# 03_POWER.net
KiCad netlist of a schematic drawn in Altium Designer
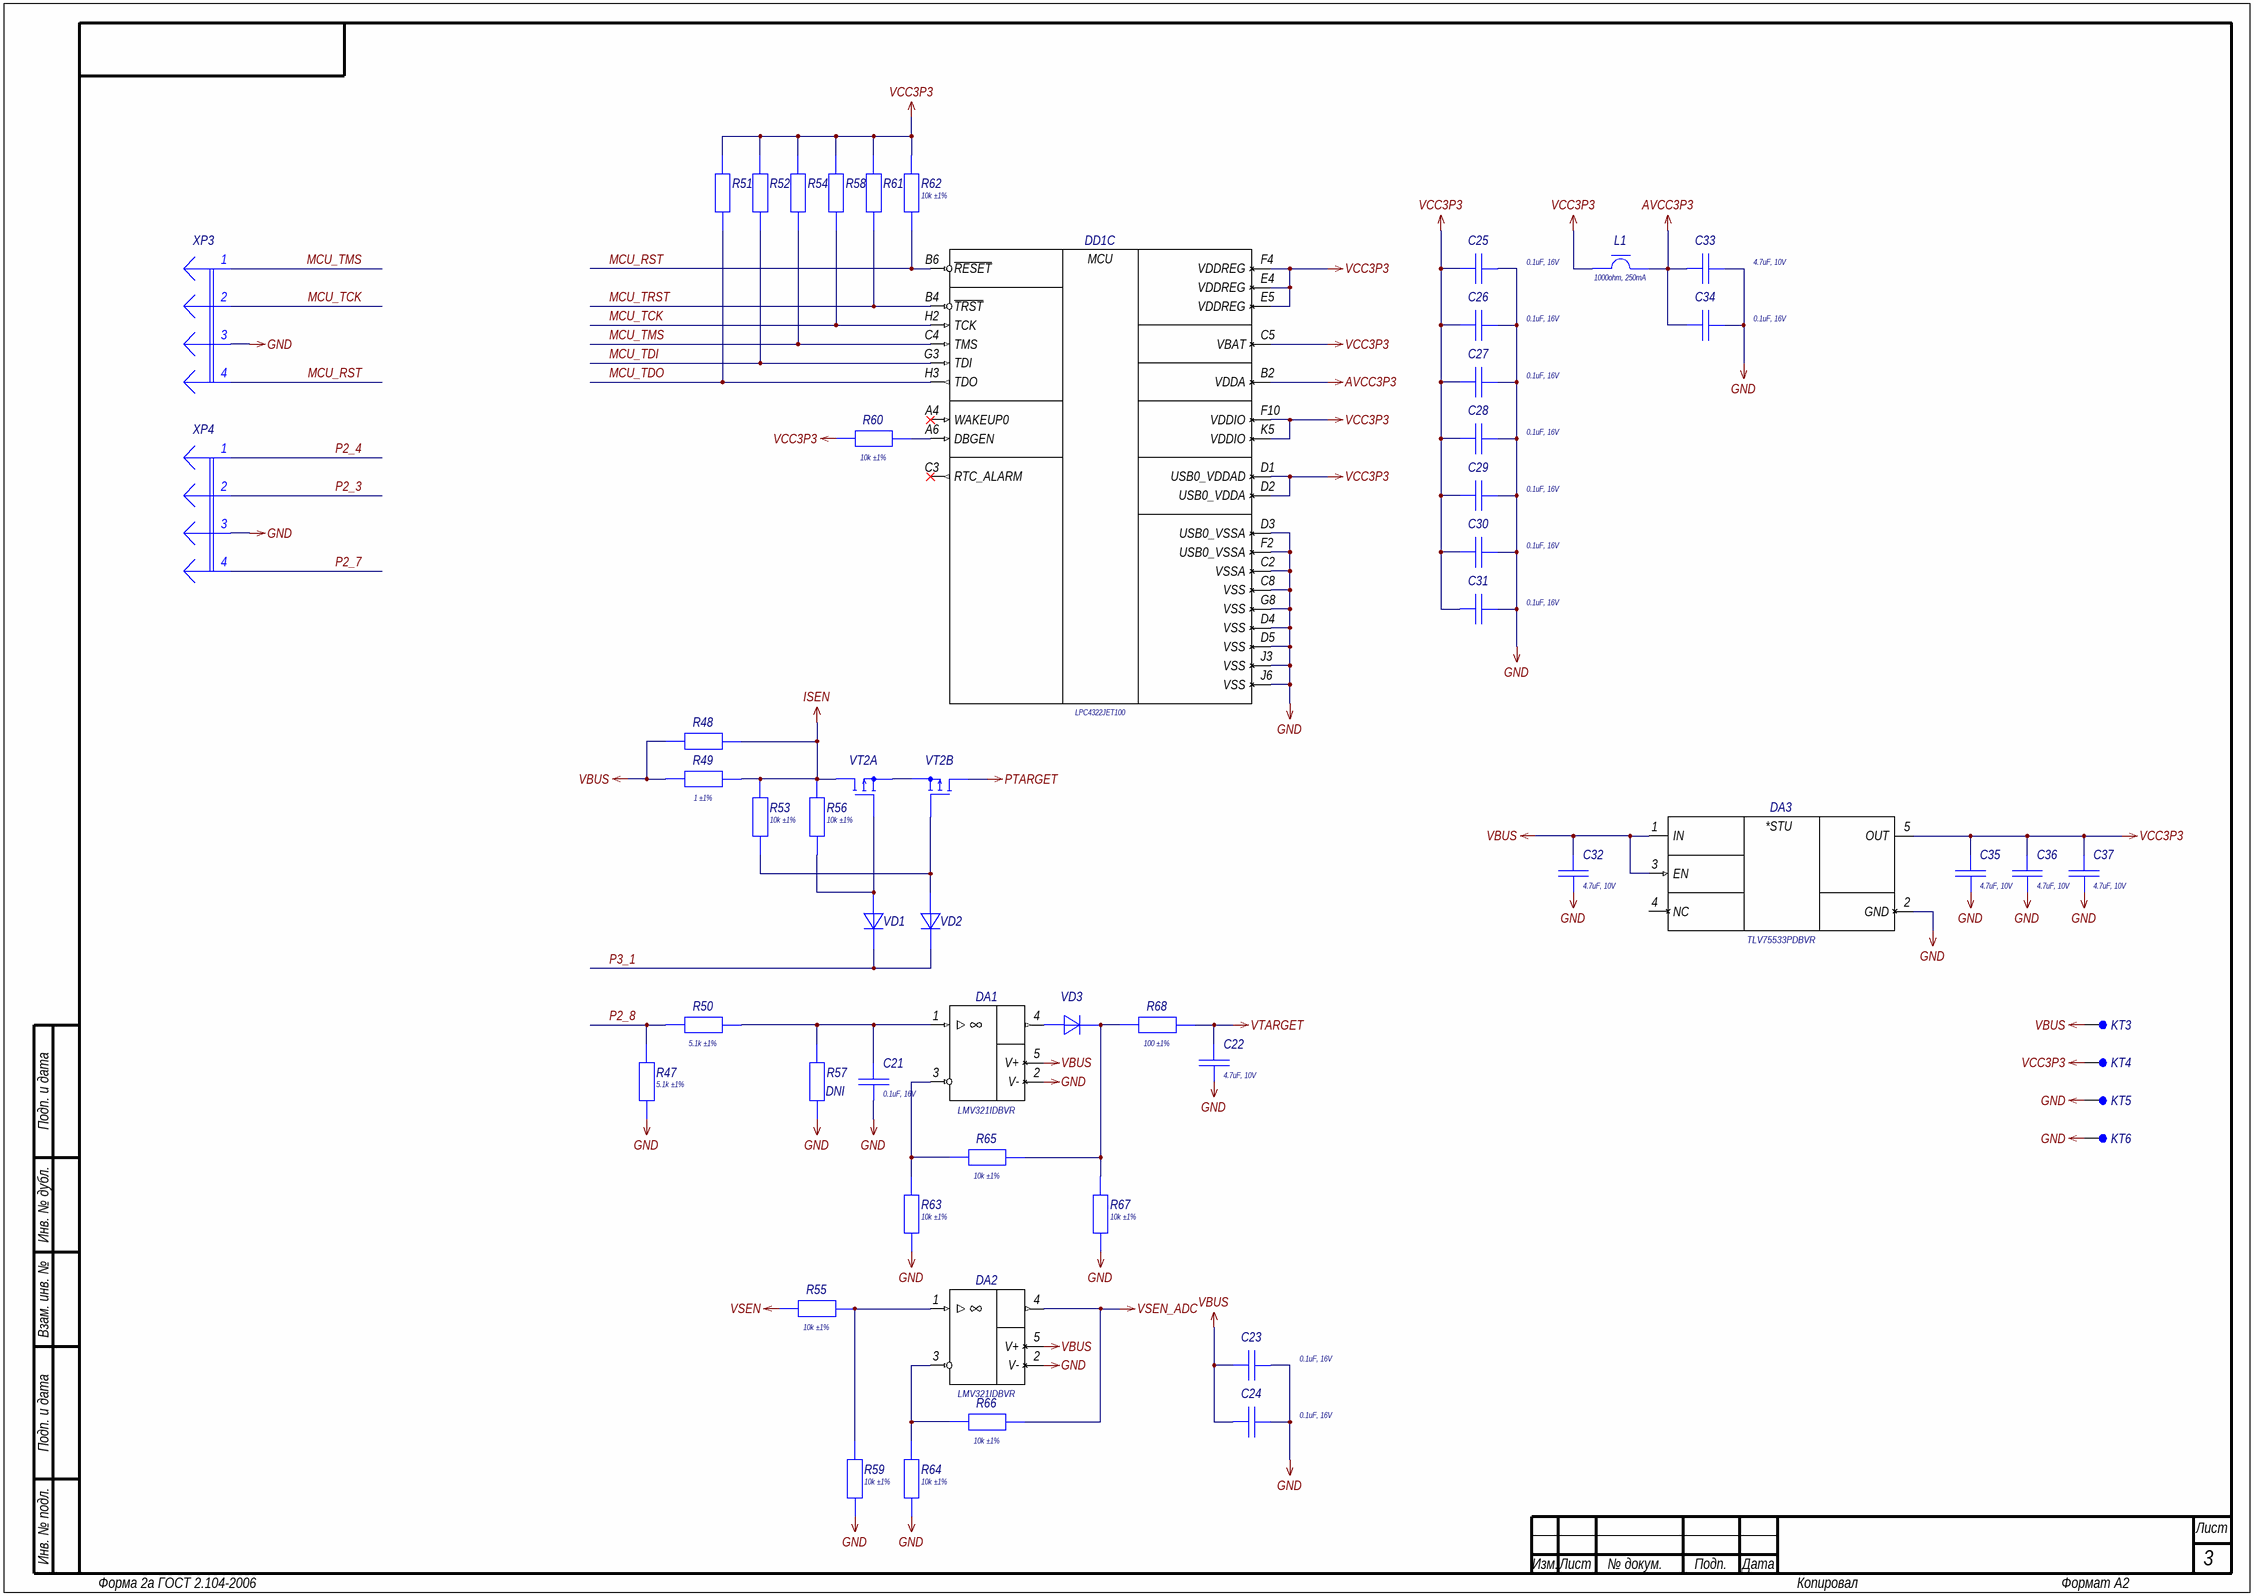
[diagram p0: 03_POWER.SchDoc]

(export (version "E")
  (design (tool "Eeschema 10.0.6"))
  (components
    (comp (ref "C21")
      (value "Capacitor")
      (footprint "C0402_100X050H050_H")
      (fields
        (field (name "PART NUMBER") "GCM155R71C104KA55D")
        (field (name "VOLTAGE") "16V")
        (field (name "TOLERANCE") "±10%")
        (field (name "SCHEMATIC VALUE") "0.1uF, 16V")
      )
      (libsource (lib "ADLib") (part "Capacitor"))
    )
    (comp (ref "C22")
      (value "Capacitor")
      (footprint "C0402_100X050H050_H")
      (fields
        (field (name "PART NUMBER") "GRM155R61A475MEAAD")
        (field (name "VOLTAGE") "10V")
        (field (name "TOLERANCE") "±20%")
        (field (name "SCHEMATIC VALUE") "4.7uF, 10V")
      )
      (libsource (lib "ADLib") (part "Capacitor"))
    )
    (comp (ref "C23")
      (value "Capacitor")
      (footprint "C0402_100X050H050_H")
      (fields
        (field (name "PART NUMBER") "GCM155R71C104KA55D")
        (field (name "VOLTAGE") "16V")
        (field (name "TOLERANCE") "±10%")
        (field (name "SCHEMATIC VALUE") "0.1uF, 16V")
      )
      (libsource (lib "ADLib") (part "Capacitor"))
    )
    (comp (ref "C24")
      (value "Capacitor")
      (footprint "C0402_100X050H050_H")
      (fields
        (field (name "PART NUMBER") "GCM155R71C104KA55D")
        (field (name "VOLTAGE") "16V")
        (field (name "TOLERANCE") "±10%")
        (field (name "SCHEMATIC VALUE") "0.1uF, 16V")
      )
      (libsource (lib "ADLib") (part "Capacitor"))
    )
    (comp (ref "C25")
      (value "Capacitor")
      (footprint "C0402_100X050H050_H")
      (fields
        (field (name "PART NUMBER") "GCM155R71C104KA55D")
        (field (name "VOLTAGE") "16V")
        (field (name "TOLERANCE") "±10%")
        (field (name "SCHEMATIC VALUE") "0.1uF, 16V")
      )
      (libsource (lib "ADLib") (part "Capacitor"))
    )
    (comp (ref "C26")
      (value "Capacitor")
      (footprint "C0402_100X050H050_H")
      (fields
        (field (name "PART NUMBER") "GCM155R71C104KA55D")
        (field (name "VOLTAGE") "16V")
        (field (name "TOLERANCE") "±10%")
        (field (name "SCHEMATIC VALUE") "0.1uF, 16V")
      )
      (libsource (lib "ADLib") (part "Capacitor"))
    )
    (comp (ref "C27")
      (value "Capacitor")
      (footprint "C0402_100X050H050_H")
      (fields
        (field (name "PART NUMBER") "GCM155R71C104KA55D")
        (field (name "VOLTAGE") "16V")
        (field (name "TOLERANCE") "±10%")
        (field (name "SCHEMATIC VALUE") "0.1uF, 16V")
      )
      (libsource (lib "ADLib") (part "Capacitor"))
    )
    (comp (ref "C28")
      (value "Capacitor")
      (footprint "C0402_100X050H050_H")
      (fields
        (field (name "PART NUMBER") "GCM155R71C104KA55D")
        (field (name "VOLTAGE") "16V")
        (field (name "TOLERANCE") "±10%")
        (field (name "SCHEMATIC VALUE") "0.1uF, 16V")
      )
      (libsource (lib "ADLib") (part "Capacitor"))
    )
    (comp (ref "C29")
      (value "Capacitor")
      (footprint "C0402_100X050H050_H")
      (fields
        (field (name "PART NUMBER") "GCM155R71C104KA55D")
        (field (name "VOLTAGE") "16V")
        (field (name "TOLERANCE") "±10%")
        (field (name "SCHEMATIC VALUE") "0.1uF, 16V")
      )
      (libsource (lib "ADLib") (part "Capacitor"))
    )
    (comp (ref "C30")
      (value "Capacitor")
      (footprint "C0402_100X050H050_H")
      (fields
        (field (name "PART NUMBER") "GCM155R71C104KA55D")
        (field (name "VOLTAGE") "16V")
        (field (name "TOLERANCE") "±10%")
        (field (name "SCHEMATIC VALUE") "0.1uF, 16V")
      )
      (libsource (lib "ADLib") (part "Capacitor"))
    )
    (comp (ref "C31")
      (value "Capacitor")
      (footprint "C0402_100X050H050_H")
      (fields
        (field (name "PART NUMBER") "GCM155R71C104KA55D")
        (field (name "VOLTAGE") "16V")
        (field (name "TOLERANCE") "±10%")
        (field (name "SCHEMATIC VALUE") "0.1uF, 16V")
      )
      (libsource (lib "ADLib") (part "Capacitor"))
    )
    (comp (ref "C32")
      (value "Capacitor")
      (footprint "C0402_100X050H050_H")
      (fields
        (field (name "PART NUMBER") "GRM155R61A475MEAAD")
        (field (name "VOLTAGE") "10V")
        (field (name "TOLERANCE") "±20%")
        (field (name "SCHEMATIC VALUE") "4.7uF, 10V")
      )
      (libsource (lib "ADLib") (part "Capacitor"))
    )
    (comp (ref "C33")
      (value "Capacitor")
      (footprint "C0402_100X050H050_H")
      (fields
        (field (name "PART NUMBER") "GRM155R61A475MEAAD")
        (field (name "VOLTAGE") "10V")
        (field (name "TOLERANCE") "±20%")
        (field (name "SCHEMATIC VALUE") "4.7uF, 10V")
      )
      (libsource (lib "ADLib") (part "Capacitor"))
    )
    (comp (ref "C34")
      (value "Capacitor")
      (footprint "C0402_100X050H050_H")
      (fields
        (field (name "PART NUMBER") "GCM155R71C104KA55D")
        (field (name "VOLTAGE") "16V")
        (field (name "TOLERANCE") "±10%")
        (field (name "SCHEMATIC VALUE") "0.1uF, 16V")
      )
      (libsource (lib "ADLib") (part "Capacitor"))
    )
    (comp (ref "C35")
      (value "Capacitor")
      (footprint "C0402_100X050H050_H")
      (fields
        (field (name "PART NUMBER") "GRM155R61A475MEAAD")
        (field (name "VOLTAGE") "10V")
        (field (name "TOLERANCE") "±20%")
        (field (name "SCHEMATIC VALUE") "4.7uF, 10V")
      )
      (libsource (lib "ADLib") (part "Capacitor"))
    )
    (comp (ref "C36")
      (value "Capacitor")
      (footprint "C0402_100X050H050_H")
      (fields
        (field (name "PART NUMBER") "GRM155R61A475MEAAD")
        (field (name "VOLTAGE") "10V")
        (field (name "TOLERANCE") "±20%")
        (field (name "SCHEMATIC VALUE") "4.7uF, 10V")
      )
      (libsource (lib "ADLib") (part "Capacitor"))
    )
    (comp (ref "C37")
      (value "Capacitor")
      (footprint "C0402_100X050H050_H")
      (fields
        (field (name "PART NUMBER") "GRM155R61A475MEAAD")
        (field (name "VOLTAGE") "10V")
        (field (name "TOLERANCE") "±20%")
        (field (name "SCHEMATIC VALUE") "4.7uF, 10V")
      )
      (libsource (lib "ADLib") (part "Capacitor"))
    )
    (comp (ref "DA1")
      (value "OPA-1-5p_2")
      (footprint "SOT-23-5_095P290X160X145_N")
      (fields
        (field (name "SCHEMATIC VALUE") "LMV321IDBVR")
        (field (name "PART NUMBER") "LMV321IDBVR")
        (field (name "MANUFACTURER") "Texas Instruments")
        (field (name "LCSC PART") "C7972")
        (field (name "PUBLISHER") "Andrew Danich")
      )
      (libsource (lib "ADLib") (part "OPA-1-5p_2"))
    )
    (comp (ref "DA2")
      (value "OPA-1-5p_2")
      (footprint "SOT-23-5_095P290X160X145_N")
      (fields
        (field (name "SCHEMATIC VALUE") "LMV321IDBVR")
        (field (name "PART NUMBER") "LMV321IDBVR")
        (field (name "MANUFACTURER") "Texas Instruments")
        (field (name "LCSC PART") "C7972")
        (field (name "PUBLISHER") "Andrew Danich")
      )
      (libsource (lib "ADLib") (part "OPA-1-5p_2"))
    )
    (comp (ref "DA3")
      (value "TLV755xxPDBV-Series")
      (footprint "SOT-23-5_095P290X160X145_N")
      (fields
        (field (name "SCHEMATIC VALUE") "TLV75533PDBVR")
        (field (name "PART NUMBER") "TLV75533PDBVR")
        (field (name "LCSC PART") "C404027")
        (field (name "MANUFACTURER") "Texas Instruments")
        (field (name "PUBLISHER") "Andrew Danich")
      )
      (libsource (lib "ADLib") (part "TLV755xxPDBV-Series"))
    )
    (comp (ref "DD1")
      (value "LPC43xxJET100-Series")
      (footprint "TFBGA-100_080P900X900X120_N")
      (fields
        (field (name "SCHEMATIC VALUE") "LPC4322JET100")
        (field (name "PART NUMBER") "LPC4322JET100")
        (field (name "MANUFACTURER") "NXP Semiconductors")
      )
      (libsource (lib "ADLib") (part "LPC43xxJET100-Series"))
    )
    (comp (ref "KT3")
      (value "Text")
      (footprint "TP-SMT-C-1mm")
      (fields (field (name "PART NUMBER") "TestPoint-SMT") (field (name "PUBLISHER") "Andrew Danich"))
      (libsource (lib "ADLib") (part "TP-S-1"))
    )
    (comp (ref "KT4")
      (value "Text")
      (footprint "TP-SMT-C-1mm")
      (fields (field (name "PART NUMBER") "TestPoint-SMT") (field (name "PUBLISHER") "Andrew Danich"))
      (libsource (lib "ADLib") (part "TP-S-1"))
    )
    (comp (ref "KT5")
      (value "Text")
      (footprint "TP-SMT-R-1.0mm")
      (fields (field (name "PART NUMBER") "TestPoint-SMT-GND") (field (name "PUBLISHER") "Andrew Danich"))
      (libsource (lib "ADLib") (part "TP-S-1"))
    )
    (comp (ref "KT6")
      (value "Text")
      (footprint "TP-SMT-R-1.0mm")
      (fields (field (name "PART NUMBER") "TestPoint-SMT-GND") (field (name "PUBLISHER") "Andrew Danich"))
      (libsource (lib "ADLib") (part "TP-S-1"))
    )
    (comp (ref "L1")
      (value "FerriteBead")
      (footprint "L0402_100X050H050_H")
      (fields
        (field (name "PART NUMBER") "BLM15HD102SN1D")
        (field (name "TOLERANCE") "±25%")
        (field (name "MANUFACTURER") "Murata")
        (field (name "SCHEMATIC VALUE") "1000ohm, 250mA")
      )
      (libsource (lib "ADLib") (part "FerriteBead"))
    )
    (comp (ref "R47")
      (value "Resistor")
      (footprint "R0402_100X050H035_H")
      (fields
        (field (name "PART NUMBER") "0402WGF5101TCE")
        (field (name "TOLERANCE") "±1%")
        (field (name "MANUFACTURER") "Uniroyal Elec")
        (field (name "SCHEMATIC VALUE") "5.1k ±1%")
      )
      (libsource (lib "ADLib") (part "Resistor"))
    )
    (comp (ref "R48")
      (value "Resistor")
      (footprint "R0402_100X050H035_H")
      (fields
        (field (name "PART NUMBER") "RC0402FR-071RL")
        (field (name "TOLERANCE") "±1%")
        (field (name "MANUFACTURER") "Yageo")
      )
      (libsource (lib "ADLib") (part "Resistor"))
    )
    (comp (ref "R49")
      (value "Resistor")
      (footprint "R0402_100X050H035_H")
      (fields
        (field (name "PART NUMBER") "RC0402FR-071RL")
        (field (name "TOLERANCE") "±1%")
        (field (name "MANUFACTURER") "Yageo")
        (field (name "SCHEMATIC VALUE") "1 ±1%")
      )
      (libsource (lib "ADLib") (part "Resistor"))
    )
    (comp (ref "R50")
      (value "Resistor")
      (footprint "R0402_100X050H035_H")
      (fields
        (field (name "PART NUMBER") "0402WGF5101TCE")
        (field (name "TOLERANCE") "±1%")
        (field (name "MANUFACTURER") "Uniroyal Elec")
        (field (name "SCHEMATIC VALUE") "5.1k ±1%")
      )
      (libsource (lib "ADLib") (part "Resistor"))
    )
    (comp (ref "R51")
      (value "Resistor")
      (footprint "R0402_100X050H035_H")
      (fields
        (field (name "PART NUMBER") "0402WGF1002TCE")
        (field (name "TOLERANCE") "±1%")
        (field (name "MANUFACTURER") "Uniroyal Elec")
      )
      (libsource (lib "ADLib") (part "Resistor"))
    )
    (comp (ref "R52")
      (value "Resistor")
      (footprint "R0402_100X050H035_H")
      (fields
        (field (name "PART NUMBER") "0402WGF1002TCE")
        (field (name "TOLERANCE") "±1%")
        (field (name "MANUFACTURER") "Uniroyal Elec")
      )
      (libsource (lib "ADLib") (part "Resistor"))
    )
    (comp (ref "R53")
      (value "Resistor")
      (footprint "R0402_100X050H035_H")
      (fields
        (field (name "PART NUMBER") "0402WGF1002TCE")
        (field (name "TOLERANCE") "±1%")
        (field (name "MANUFACTURER") "Uniroyal Elec")
        (field (name "SCHEMATIC VALUE") "10k ±1%")
      )
      (libsource (lib "ADLib") (part "Resistor"))
    )
    (comp (ref "R54")
      (value "Resistor")
      (footprint "R0402_100X050H035_H")
      (fields
        (field (name "PART NUMBER") "0402WGF1002TCE")
        (field (name "TOLERANCE") "±1%")
        (field (name "MANUFACTURER") "Uniroyal Elec")
      )
      (libsource (lib "ADLib") (part "Resistor"))
    )
    (comp (ref "R55")
      (value "Resistor")
      (footprint "R0402_100X050H035_H")
      (fields
        (field (name "PART NUMBER") "0402WGF1002TCE")
        (field (name "TOLERANCE") "±1%")
        (field (name "MANUFACTURER") "Uniroyal Elec")
        (field (name "SCHEMATIC VALUE") "10k ±1%")
      )
      (libsource (lib "ADLib") (part "Resistor"))
    )
    (comp (ref "R56")
      (value "Resistor")
      (footprint "R0402_100X050H035_H")
      (fields
        (field (name "PART NUMBER") "0402WGF1002TCE")
        (field (name "TOLERANCE") "±1%")
        (field (name "MANUFACTURER") "Uniroyal Elec")
        (field (name "SCHEMATIC VALUE") "10k ±1%")
      )
      (libsource (lib "ADLib") (part "Resistor"))
    )
    (comp (ref "R57")
      (value "Resistor")
      (footprint "R0402_100X050H035_H")
      (fields
        (field (name "PART NUMBER") "0402WGF5101TCE")
        (field (name "TOLERANCE") "±1%")
        (field (name "MANUFACTURER") "Uniroyal Elec")
      )
      (libsource (lib "ADLib") (part "Resistor"))
    )
    (comp (ref "R58")
      (value "Resistor")
      (footprint "R0402_100X050H035_H")
      (fields
        (field (name "PART NUMBER") "0402WGF1002TCE")
        (field (name "TOLERANCE") "±1%")
        (field (name "MANUFACTURER") "Uniroyal Elec")
      )
      (libsource (lib "ADLib") (part "Resistor"))
    )
    (comp (ref "R59")
      (value "Resistor")
      (footprint "R0402_100X050H035_H")
      (fields
        (field (name "PART NUMBER") "0402WGF1002TCE")
        (field (name "TOLERANCE") "±1%")
        (field (name "MANUFACTURER") "Uniroyal Elec")
        (field (name "SCHEMATIC VALUE") "10k ±1%")
      )
      (libsource (lib "ADLib") (part "Resistor"))
    )
    (comp (ref "R60")
      (value "Resistor")
      (footprint "R0402_100X050H035_H")
      (fields
        (field (name "PART NUMBER") "0402WGF1002TCE")
        (field (name "TOLERANCE") "±1%")
        (field (name "MANUFACTURER") "Uniroyal Elec")
        (field (name "SCHEMATIC VALUE") "10k ±1%")
      )
      (libsource (lib "ADLib") (part "Resistor"))
    )
    (comp (ref "R61")
      (value "Resistor")
      (footprint "R0402_100X050H035_H")
      (fields
        (field (name "PART NUMBER") "0402WGF1002TCE")
        (field (name "TOLERANCE") "±1%")
        (field (name "MANUFACTURER") "Uniroyal Elec")
      )
      (libsource (lib "ADLib") (part "Resistor"))
    )
    (comp (ref "R62")
      (value "Resistor")
      (footprint "R0402_100X050H035_H")
      (fields
        (field (name "PART NUMBER") "0402WGF1002TCE")
        (field (name "TOLERANCE") "±1%")
        (field (name "MANUFACTURER") "Uniroyal Elec")
        (field (name "SCHEMATIC VALUE") "10k ±1%")
      )
      (libsource (lib "ADLib") (part "Resistor"))
    )
    (comp (ref "R63")
      (value "Resistor")
      (footprint "R0402_100X050H035_H")
      (fields
        (field (name "PART NUMBER") "0402WGF1002TCE")
        (field (name "TOLERANCE") "±1%")
        (field (name "MANUFACTURER") "Uniroyal Elec")
        (field (name "SCHEMATIC VALUE") "10k ±1%")
      )
      (libsource (lib "ADLib") (part "Resistor"))
    )
    (comp (ref "R64")
      (value "Resistor")
      (footprint "R0402_100X050H035_H")
      (fields
        (field (name "PART NUMBER") "0402WGF1002TCE")
        (field (name "TOLERANCE") "±1%")
        (field (name "MANUFACTURER") "Uniroyal Elec")
        (field (name "SCHEMATIC VALUE") "10k ±1%")
      )
      (libsource (lib "ADLib") (part "Resistor"))
    )
    (comp (ref "R65")
      (value "Resistor")
      (footprint "R0402_100X050H035_H")
      (fields
        (field (name "PART NUMBER") "0402WGF1002TCE")
        (field (name "TOLERANCE") "±1%")
        (field (name "MANUFACTURER") "Uniroyal Elec")
        (field (name "SCHEMATIC VALUE") "10k ±1%")
      )
      (libsource (lib "ADLib") (part "Resistor"))
    )
    (comp (ref "R66")
      (value "Resistor")
      (footprint "R0402_100X050H035_H")
      (fields
        (field (name "PART NUMBER") "0402WGF1002TCE")
        (field (name "TOLERANCE") "±1%")
        (field (name "MANUFACTURER") "Uniroyal Elec")
        (field (name "SCHEMATIC VALUE") "10k ±1%")
      )
      (libsource (lib "ADLib") (part "Resistor"))
    )
    (comp (ref "R67")
      (value "Resistor")
      (footprint "R0402_100X050H035_H")
      (fields
        (field (name "PART NUMBER") "0402WGF1002TCE")
        (field (name "TOLERANCE") "±1%")
        (field (name "MANUFACTURER") "Uniroyal Elec")
        (field (name "SCHEMATIC VALUE") "10k ±1%")
      )
      (libsource (lib "ADLib") (part "Resistor"))
    )
    (comp (ref "R68")
      (value "Resistor")
      (footprint "R0402_100X050H035_H")
      (fields
        (field (name "PART NUMBER") "RC0402FR-07100RL")
        (field (name "TOLERANCE") "±1%")
        (field (name "MANUFACTURER") "Yageo")
        (field (name "SCHEMATIC VALUE") "100 ±1%")
      )
      (libsource (lib "ADLib") (part "Resistor"))
    )
    (comp (ref "VD1")
      (value "Diode")
      (footprint "SOD-523")
      (fields
        (field (name "PART NUMBER") "1N4148WT-7")
        (field (name "LCSC PART") "C83482")
        (field (name "MANUFACTURER") "Diodes Incorporated")
      )
      (libsource (lib "ADLib") (part "Diode"))
    )
    (comp (ref "VD2")
      (value "Diode")
      (footprint "SOD-523")
      (fields
        (field (name "PART NUMBER") "1N4148WT-7")
        (field (name "LCSC PART") "C83482")
        (field (name "MANUFACTURER") "Diodes Incorporated")
      )
      (libsource (lib "ADLib") (part "Diode"))
    )
    (comp (ref "VD3")
      (value "Diode")
      (footprint "SOD-523")
      (fields
        (field (name "PART NUMBER") "1N4148WT-7")
        (field (name "LCSC PART") "C83482")
        (field (name "MANUFACTURER") "Diodes Incorporated")
      )
      (libsource (lib "ADLib") (part "Diode"))
    )
    (comp (ref "VT2")
      (value "MOSFET-PP_8p_2")
      (footprint "SOT-1118-2M_065P200X200X065_N")
      (fields
        (field (name "PART NUMBER") "PMDPB55XP,115")
        (field (name "LCSC PART") "C552752")
        (field (name "MANUFACTURER") "NXP Semiconductors")
        (field (name "PUBLISHER") "Andrew Danich")
      )
      (libsource (lib "") (part "MOSFET-PP_8p_2_1"))
    )
    (comp (ref "XP3")
      (value "Text")
      (footprint "PLS-4")
      (fields (field (name "PART NUMBER") "PLS-4"))
      (libsource (lib "ADLib") (part "Con-4-M"))
    )
    (comp (ref "XP4")
      (value "Text")
      (footprint "PLS-4")
      (fields (field (name "PART NUMBER") "PLS-4"))
      (libsource (lib "ADLib") (part "Con-4-M"))
    )
  )
  (nets
    (net (code "1") (name "/MCU_RST") (class "Default")
      (node (ref "DD1") (pin "B6") (pinfunction "~{RESET}_B6") (pintype "input"))
      (node (ref "R62") (pin "1") (pinfunction "1_1") (pintype "passive"))
      (node (ref "XP3") (pin "4") (pintype "passive"))
    )
    (net (code "2") (name "/MCU_TCK") (class "Default")
      (node (ref "DD1") (pin "H2") (pinfunction "TCK_H2") (pintype "input"))
      (node (ref "R58") (pin "1") (pinfunction "1_1") (pintype "passive"))
      (node (ref "XP3") (pin "2") (pintype "passive"))
    )
    (net (code "3") (name "/MCU_TDI") (class "Default")
      (node (ref "DD1") (pin "G3") (pinfunction "TDI_G3") (pintype "input"))
      (node (ref "R52") (pin "1") (pinfunction "1_1") (pintype "passive"))
    )
    (net (code "4") (name "/MCU_TDO") (class "Default")
      (node (ref "DD1") (pin "H3") (pinfunction "TDO_H3") (pintype "output"))
      (node (ref "R51") (pin "1") (pinfunction "1_1") (pintype "passive"))
    )
    (net (code "5") (name "/MCU_TMS") (class "Default")
      (node (ref "DD1") (pin "C4") (pinfunction "TMS_C4") (pintype "input"))
      (node (ref "R54") (pin "1") (pinfunction "1_1") (pintype "passive"))
      (node (ref "XP3") (pin "1") (pintype "passive"))
    )
    (net (code "6") (name "/MCU_TRST") (class "Default")
      (node (ref "DD1") (pin "B4") (pinfunction "~{TRST}_B4") (pintype "input"))
      (node (ref "R61") (pin "1") (pinfunction "1_1") (pintype "passive"))
    )
    (net (code "7") (name "/P2_3") (class "Default") (node (ref "XP4") (pin "2") (pintype "passive")))
    (net (code "8") (name "/P2_4") (class "Default") (node (ref "XP4") (pin "1") (pintype "passive")))
    (net (code "9") (name "/P2_7") (class "Default") (node (ref "XP4") (pin "4") (pintype "passive")))
    (net (code "10") (name "/P2_8") (class "Default")
      (node (ref "R47") (pin "2") (pinfunction "2_2") (pintype "passive"))
      (node (ref "R50") (pin "2") (pinfunction "2_2") (pintype "passive"))
    )
    (net (code "11") (name "/P3_1") (class "Default")
      (node (ref "VD1") (pin "2") (pinfunction "К_2") (pintype "passive"))
      (node (ref "VD2") (pin "2") (pinfunction "К_2") (pintype "passive"))
    )
    (net (code "12") (name "AVCC3P3") (class "Default")
      (node (ref "C33") (pin "2") (pinfunction "2_2") (pintype "passive"))
      (node (ref "C34") (pin "2") (pinfunction "2_2") (pintype "passive"))
      (node (ref "DD1") (pin "B2") (pinfunction "VDDA_B2") (pintype "power_in"))
      (node (ref "L1") (pin "2") (pinfunction "2_2") (pintype "passive"))
    )
    (net (code "13") (name "GND") (class "Default")
      (node (ref "C21") (pin "1") (pinfunction "1_1") (pintype "passive"))
      (node (ref "C22") (pin "1") (pinfunction "1_1") (pintype "passive"))
      (node (ref "C23") (pin "1") (pinfunction "1_1") (pintype "passive"))
      (node (ref "C24") (pin "1") (pinfunction "1_1") (pintype "passive"))
      (node (ref "C25") (pin "1") (pinfunction "1_1") (pintype "passive"))
      (node (ref "C26") (pin "1") (pinfunction "1_1") (pintype "passive"))
      (node (ref "C27") (pin "1") (pinfunction "1_1") (pintype "passive"))
      (node (ref "C28") (pin "1") (pinfunction "1_1") (pintype "passive"))
      (node (ref "C29") (pin "1") (pinfunction "1_1") (pintype "passive"))
      (node (ref "C30") (pin "1") (pinfunction "1_1") (pintype "passive"))
      (node (ref "C31") (pin "1") (pinfunction "1_1") (pintype "passive"))
      (node (ref "C32") (pin "2") (pinfunction "2_2") (pintype "passive"))
      (node (ref "C33") (pin "1") (pinfunction "1_1") (pintype "passive"))
      (node (ref "C34") (pin "1") (pinfunction "1_1") (pintype "passive"))
      (node (ref "C35") (pin "2") (pinfunction "2_2") (pintype "passive"))
      (node (ref "C36") (pin "2") (pinfunction "2_2") (pintype "passive"))
      (node (ref "C37") (pin "2") (pinfunction "2_2") (pintype "passive"))
      (node (ref "DA1") (pin "2") (pinfunction "V-_2") (pintype "power_in"))
      (node (ref "DA2") (pin "2") (pinfunction "V-_2") (pintype "power_in"))
      (node (ref "DA3") (pin "2") (pinfunction "GND_2") (pintype "power_in"))
      (node (ref "DD1") (pin "C2") (pinfunction "VSSA_C2") (pintype "power_in"))
      (node (ref "DD1") (pin "C8") (pinfunction "VSS_C8") (pintype "power_in"))
      (node (ref "DD1") (pin "D3") (pinfunction "USB0_VSSA_D3") (pintype "power_in"))
      (node (ref "DD1") (pin "D4") (pinfunction "VSS_D4") (pintype "power_in"))
      (node (ref "DD1") (pin "D5") (pinfunction "VSS_D5") (pintype "power_in"))
      (node (ref "DD1") (pin "F2") (pinfunction "USB0_VSSA_F2") (pintype "power_in"))
      (node (ref "DD1") (pin "G8") (pinfunction "VSS_G8") (pintype "power_in"))
      (node (ref "DD1") (pin "J3") (pinfunction "VSS_J3") (pintype "power_in"))
      (node (ref "DD1") (pin "J6") (pinfunction "VSS_J6") (pintype "power_in"))
      (node (ref "KT5") (pin "1") (pinfunction "1_1") (pintype "passive"))
      (node (ref "KT6") (pin "1") (pinfunction "1_1") (pintype "passive"))
      (node (ref "R47") (pin "1") (pinfunction "1_1") (pintype "passive"))
      (node (ref "R57") (pin "1") (pinfunction "1_1") (pintype "passive"))
      (node (ref "R59") (pin "2") (pinfunction "2_2") (pintype "passive"))
      (node (ref "R63") (pin "2") (pinfunction "2_2") (pintype "passive"))
      (node (ref "R64") (pin "2") (pinfunction "2_2") (pintype "passive"))
      (node (ref "R67") (pin "2") (pinfunction "2_2") (pintype "passive"))
      (node (ref "XP3") (pin "3") (pintype "passive"))
      (node (ref "XP4") (pin "3") (pintype "passive"))
    )
    (net (code "14") (name "ISEN") (class "Default")
      (node (ref "R48") (pin "2") (pinfunction "2_2") (pintype "passive"))
      (node (ref "R49") (pin "2") (pinfunction "2_2") (pintype "passive"))
      (node (ref "R53") (pin "2") (pinfunction "2_2") (pintype "passive"))
      (node (ref "R56") (pin "2") (pinfunction "2_2") (pintype "passive"))
      (node (ref "VT2") (pin "6") (pinfunction "D1_6") (pintype "passive"))
    )
    (net (code "15") (name "Net-(DA1-IN+)") (class "Default")
      (node (ref "C21") (pin "2") (pinfunction "2_2") (pintype "passive"))
      (node (ref "DA1") (pin "1") (pinfunction "IN+_1") (pintype "input"))
      (node (ref "R50") (pin "1") (pinfunction "1_1") (pintype "passive"))
      (node (ref "R57") (pin "2") (pinfunction "2_2") (pintype "passive"))
    )
    (net (code "16") (name "Net-(DA1-IN-)") (class "Default")
      (node (ref "DA1") (pin "3") (pinfunction "IN-_3") (pintype "input"))
      (node (ref "R63") (pin "1") (pinfunction "1_1") (pintype "passive"))
      (node (ref "R65") (pin "1") (pinfunction "1_1") (pintype "passive"))
    )
    (net (code "17") (name "Net-(DA1-OUT)") (class "Default")
      (node (ref "DA1") (pin "4") (pinfunction "OUT_4") (pintype "output"))
      (node (ref "VD3") (pin "1") (pinfunction "А_1") (pintype "passive"))
    )
    (net (code "18") (name "Net-(DA2-IN+)") (class "Default")
      (node (ref "DA2") (pin "1") (pinfunction "IN+_1") (pintype "input"))
      (node (ref "R55") (pin "2") (pinfunction "2_2") (pintype "passive"))
      (node (ref "R59") (pin "1") (pinfunction "1_1") (pintype "passive"))
    )
    (net (code "19") (name "Net-(DA2-IN-)") (class "Default")
      (node (ref "DA2") (pin "3") (pinfunction "IN-_3") (pintype "input"))
      (node (ref "R64") (pin "1") (pinfunction "1_1") (pintype "passive"))
      (node (ref "R66") (pin "1") (pinfunction "1_1") (pintype "passive"))
    )
    (net (code "20") (name "Net-(DD1C-DBGEN)") (class "Default")
      (node (ref "DD1") (pin "A6") (pinfunction "DBGEN_A6") (pintype "input"))
      (node (ref "R60") (pin "2") (pinfunction "2_2") (pintype "passive"))
    )
    (net (code "21") (name "Net-(VD1-А)") (class "Default")
      (node (ref "R56") (pin "1") (pinfunction "1_1") (pintype "passive"))
      (node (ref "VD1") (pin "1") (pinfunction "А_1") (pintype "passive"))
      (node (ref "VT2") (pin "2") (pinfunction "G1_2") (pintype "passive"))
    )
    (net (code "22") (name "Net-(VD2-А)") (class "Default")
      (node (ref "R53") (pin "1") (pinfunction "1_1") (pintype "passive"))
      (node (ref "VD2") (pin "1") (pinfunction "А_1") (pintype "passive"))
      (node (ref "VT2") (pin "5") (pinfunction "G2_5") (pintype "passive"))
    )
    (net (code "23") (name "Net-(VD3-К)") (class "Default")
      (node (ref "R65") (pin "2") (pinfunction "2_2") (pintype "passive"))
      (node (ref "R67") (pin "1") (pinfunction "1_1") (pintype "passive"))
      (node (ref "R68") (pin "1") (pinfunction "1_1") (pintype "passive"))
      (node (ref "VD3") (pin "2") (pinfunction "К_2") (pintype "passive"))
    )
    (net (code "24") (name "Net-(VT2A-S1)") (class "Default")
      (node (ref "VT2") (pin "1") (pinfunction "S1_1") (pintype "passive"))
      (node (ref "VT2") (pin "4") (pinfunction "S2_4") (pintype "passive"))
    )
    (net (code "25") (name "PTARGET") (class "Default")
      (node (ref "VT2") (pin "3") (pinfunction "D2_3") (pintype "passive"))
    )
    (net (code "26") (name "VBUS") (class "Default")
      (node (ref "C23") (pin "2") (pinfunction "2_2") (pintype "passive"))
      (node (ref "C24") (pin "2") (pinfunction "2_2") (pintype "passive"))
      (node (ref "C32") (pin "1") (pinfunction "1_1") (pintype "passive"))
      (node (ref "DA1") (pin "5") (pinfunction "V+_5") (pintype "power_in"))
      (node (ref "DA2") (pin "5") (pinfunction "V+_5") (pintype "power_in"))
      (node (ref "DA3") (pin "1") (pinfunction "IN_1") (pintype "power_in"))
      (node (ref "DA3") (pin "3") (pinfunction "EN_3") (pintype "input"))
      (node (ref "KT3") (pin "1") (pinfunction "1_1") (pintype "passive"))
      (node (ref "R48") (pin "1") (pinfunction "1_1") (pintype "passive"))
      (node (ref "R49") (pin "1") (pinfunction "1_1") (pintype "passive"))
    )
    (net (code "27") (name "VCC3P3") (class "Default")
      (node (ref "C25") (pin "2") (pinfunction "2_2") (pintype "passive"))
      (node (ref "C26") (pin "2") (pinfunction "2_2") (pintype "passive"))
      (node (ref "C27") (pin "2") (pinfunction "2_2") (pintype "passive"))
      (node (ref "C28") (pin "2") (pinfunction "2_2") (pintype "passive"))
      (node (ref "C29") (pin "2") (pinfunction "2_2") (pintype "passive"))
      (node (ref "C30") (pin "2") (pinfunction "2_2") (pintype "passive"))
      (node (ref "C31") (pin "2") (pinfunction "2_2") (pintype "passive"))
      (node (ref "C35") (pin "1") (pinfunction "1_1") (pintype "passive"))
      (node (ref "C36") (pin "1") (pinfunction "1_1") (pintype "passive"))
      (node (ref "C37") (pin "1") (pinfunction "1_1") (pintype "passive"))
      (node (ref "DA3") (pin "5") (pinfunction "OUT_5") (pintype "power_in"))
      (node (ref "DD1") (pin "C5") (pinfunction "VBAT_C5") (pintype "power_in"))
      (node (ref "DD1") (pin "D1") (pinfunction "USB0_VDDAD_D1") (pintype "power_in"))
      (node (ref "DD1") (pin "D2") (pinfunction "USB0_VDDA_D2") (pintype "power_in"))
      (node (ref "DD1") (pin "E4") (pinfunction "VDDREG_E4") (pintype "power_in"))
      (node (ref "DD1") (pin "E5") (pinfunction "VDDREG_E5") (pintype "power_in"))
      (node (ref "DD1") (pin "F10") (pinfunction "VDDIO_F10") (pintype "power_in"))
      (node (ref "DD1") (pin "F4") (pinfunction "VDDREG_F4") (pintype "power_in"))
      (node (ref "DD1") (pin "K5") (pinfunction "VDDIO_K5") (pintype "power_in"))
      (node (ref "KT4") (pin "1") (pinfunction "1_1") (pintype "passive"))
      (node (ref "L1") (pin "1") (pinfunction "1_1") (pintype "passive"))
      (node (ref "R51") (pin "2") (pinfunction "2_2") (pintype "passive"))
      (node (ref "R52") (pin "2") (pinfunction "2_2") (pintype "passive"))
      (node (ref "R54") (pin "2") (pinfunction "2_2") (pintype "passive"))
      (node (ref "R58") (pin "2") (pinfunction "2_2") (pintype "passive"))
      (node (ref "R60") (pin "1") (pinfunction "1_1") (pintype "passive"))
      (node (ref "R61") (pin "2") (pinfunction "2_2") (pintype "passive"))
      (node (ref "R62") (pin "2") (pinfunction "2_2") (pintype "passive"))
    )
    (net (code "28") (name "VSEN") (class "Default")
      (node (ref "R55") (pin "1") (pinfunction "1_1") (pintype "passive"))
    )
    (net (code "29") (name "VSEN_ADC") (class "Default")
      (node (ref "DA2") (pin "4") (pinfunction "OUT_4") (pintype "output"))
      (node (ref "R66") (pin "2") (pinfunction "2_2") (pintype "passive"))
    )
    (net (code "30") (name "VTARGET") (class "Default")
      (node (ref "C22") (pin "2") (pinfunction "2_2") (pintype "passive"))
      (node (ref "R68") (pin "2") (pinfunction "2_2") (pintype "passive"))
    )
    (net (code "31") (name "unconnected-(DA3-NC-Pad4)") (class "Default")
      (node (ref "DA3") (pin "4") (pinfunction "NC_4") (pintype "passive"))
    )
    (net (code "32") (name "unconnected-(DD1C-RTC_ALARM-PadC3)") (class "Default")
      (node (ref "DD1") (pin "C3") (pinfunction "RTC_ALARM_C3") (pintype "output+no_connect"))
    )
    (net (code "33") (name "unconnected-(DD1C-WAKEUP0-PadA4)") (class "Default")
      (node (ref "DD1") (pin "A4") (pinfunction "WAKEUP0_A4") (pintype "input+no_connect"))
    )
  )
)
